# Principal.net
KiCad netlist of a schematic drawn in EAGLE
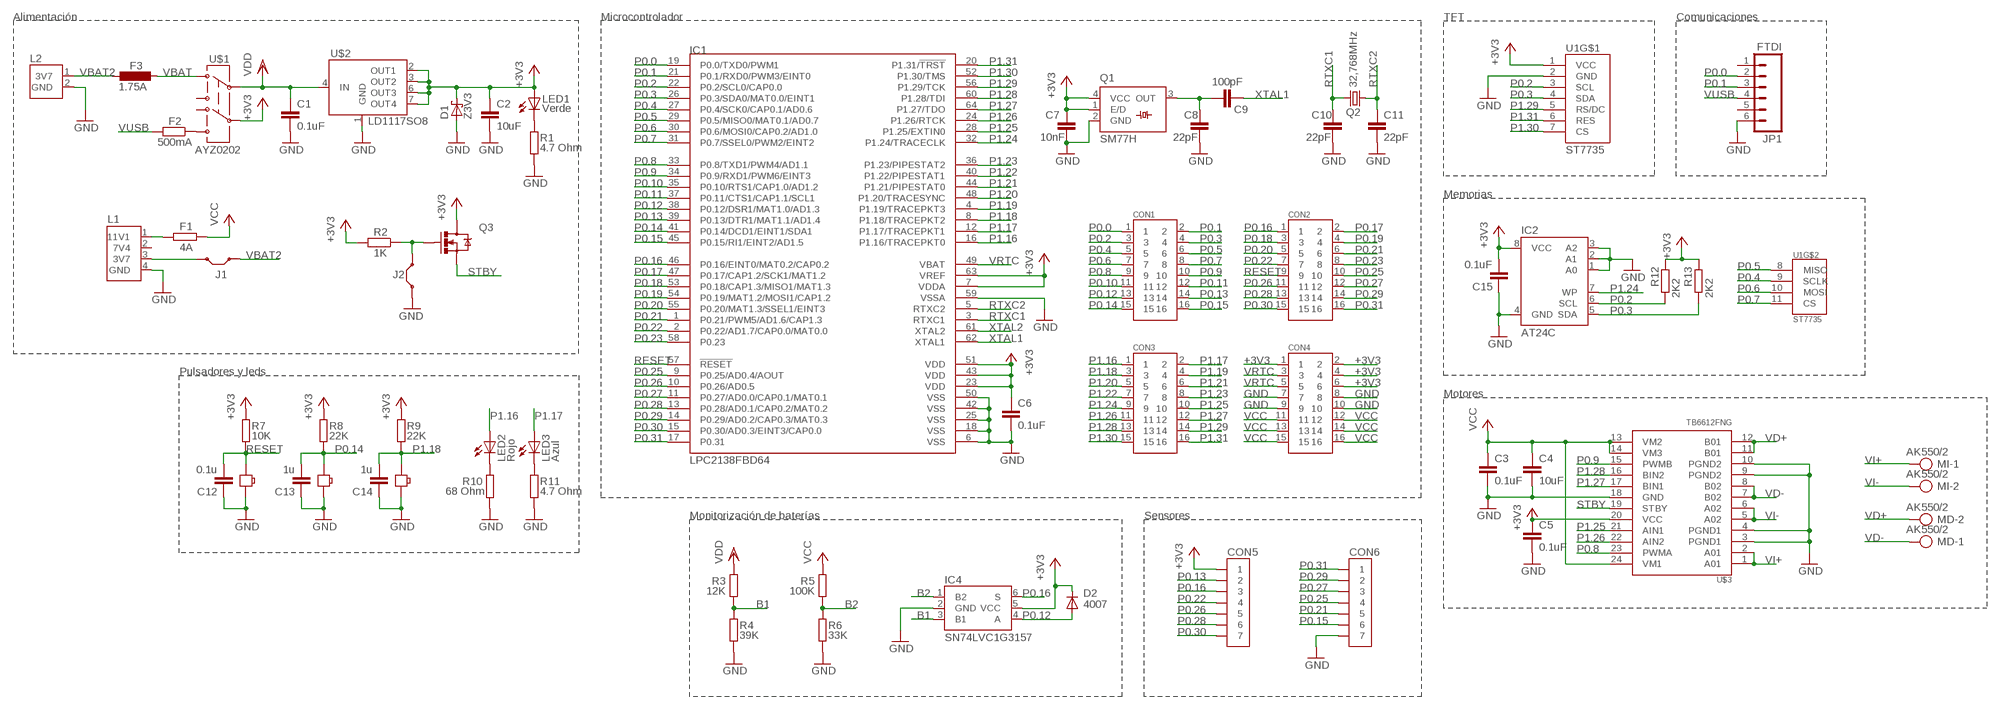
[diagram p0: schematic, sheet 1]

(export (version "E")
  (design (tool "Eeschema 10.0.6"))
  (components
    (comp (ref "B1")
      (value "BUTTON-SMD-2P")
      (footprint "eagle-import:BUTTON_2P_SMD")
      (libsource (lib "eagle-import") (part "BUTTON-SMD-2P"))
    )
    (comp (ref "C1")
      (value "0.1uF")
      (footprint "eagle-import:C0805")
      (libsource (lib "eagle-import") (part "C-EUC0805"))
    )
    (comp (ref "C2")
      (value "10uF")
      (footprint "eagle-import:C1206")
      (libsource (lib "eagle-import") (part "C-EUC1206"))
    )
    (comp (ref "C3")
      (value "0.1uF")
      (footprint "eagle-import:C0805")
      (libsource (lib "eagle-import") (part "C-EUC0805"))
    )
    (comp (ref "C4")
      (value "10uF")
      (footprint "eagle-import:C1206")
      (libsource (lib "eagle-import") (part "C-EUC1206"))
    )
    (comp (ref "C5")
      (value "0.1uF")
      (footprint "eagle-import:C0805")
      (libsource (lib "eagle-import") (part "C-EUC0805"))
    )
    (comp (ref "C6")
      (value "0.1uF")
      (footprint "eagle-import:C0805")
      (libsource (lib "eagle-import") (part "C-EUC0805"))
    )
    (comp (ref "C7")
      (value "10nF")
      (footprint "eagle-import:C0805")
      (libsource (lib "eagle-import") (part "C-EUC0805"))
    )
    (comp (ref "C8")
      (value "22pF")
      (footprint "eagle-import:C0805")
      (libsource (lib "eagle-import") (part "C-EUC0805"))
    )
    (comp (ref "C9")
      (value "100pF")
      (footprint "eagle-import:C0805")
      (libsource (lib "eagle-import") (part "C-EUC0805"))
    )
    (comp (ref "C10")
      (value "22pF")
      (footprint "eagle-import:C0805")
      (libsource (lib "eagle-import") (part "C-EUC0805"))
    )
    (comp (ref "C11")
      (value "22pF")
      (footprint "eagle-import:C0805")
      (libsource (lib "eagle-import") (part "C-EUC0805"))
    )
    (comp (ref "C12")
      (value "0.1u")
      (footprint "eagle-import:C0805")
      (libsource (lib "eagle-import") (part "C-EUC0805"))
    )
    (comp (ref "C13")
      (value "1u")
      (footprint "eagle-import:C0805")
      (libsource (lib "eagle-import") (part "C-EUC0805"))
    )
    (comp (ref "C14")
      (value "1u")
      (footprint "eagle-import:C0805")
      (libsource (lib "eagle-import") (part "C-EUC0805"))
    )
    (comp (ref "C15")
      (value "0.1uF")
      (footprint "eagle-import:C0805")
      (libsource (lib "eagle-import") (part "C-EUC0805"))
    )
    (comp (ref "CON1")
      (value "8X2_PIN_2MM_HEMBRA")
      (footprint "eagle-import:8X2_PIN_2MM")
      (libsource (lib "eagle-import") (part "8X2_PIN_2MM_HEMBRA"))
    )
    (comp (ref "CON2")
      (value "8X2_PIN_2MM_HEMBRA")
      (footprint "eagle-import:8X2_PIN_2MM")
      (libsource (lib "eagle-import") (part "8X2_PIN_2MM_HEMBRA"))
    )
    (comp (ref "CON3")
      (value "8X2_PIN_2MM_HEMBRA")
      (footprint "eagle-import:8X2_PIN_2MM")
      (libsource (lib "eagle-import") (part "8X2_PIN_2MM_HEMBRA"))
    )
    (comp (ref "CON4")
      (value "8X2_PIN_2MM_HEMBRA")
      (footprint "eagle-import:8X2_PIN_2MM")
      (libsource (lib "eagle-import") (part "8X2_PIN_2MM_HEMBRA"))
    )
    (comp (ref "CON5")
      (value "7_PINES")
      (footprint "eagle-import:7_PIN_MACHO_SMD_RA")
      (libsource (lib "eagle-import") (part "7_PINES"))
    )
    (comp (ref "CON6")
      (value "7_PINES")
      (footprint "eagle-import:7_PIN_MACHO_SMD_RA")
      (libsource (lib "eagle-import") (part "7_PINES"))
    )
    (comp (ref "D1")
      (value "Z3V3")
      (footprint "eagle-import:DO35-7")
      (libsource (lib "eagle-import") (part "SCHOTTKY-DIODEDO35-7"))
    )
    (comp (ref "D2")
      (value "4007")
      (footprint "eagle-import:SOD106-R")
      (libsource (lib "eagle-import") (part "DIODE-SOD106-R"))
    )
    (comp (ref "F1")
      (value "4A")
      (footprint "eagle-import:2920")
      (libsource (lib "eagle-import") (part "FUSIBLE"))
    )
    (comp (ref "F2")
      (value "500mA")
      (footprint "eagle-import:M1206")
      (libsource (lib "eagle-import") (part "R-EU_M1206"))
    )
    (comp (ref "F3")
      (value "1.75A")
      (footprint "eagle-import:L1812")
      (libsource (lib "eagle-import") (part "L-EUL1812"))
    )
    (comp (ref "IC1")
      (value "LPC2138FBD64")
      (footprint "eagle-import:TSQFP50P1200X1200X160-64N")
      (libsource (lib "eagle-import") (part "LPC2138FBD64"))
    )
    (comp (ref "IC2")
      (value "AT24C")
      (footprint "eagle-import:8S1")
      (libsource (lib "eagle-import") (part "AT24C"))
    )
    (comp (ref "IC4")
      (value "SN74LVC1G3157")
      (footprint "eagle-import:DBV")
      (libsource (lib "eagle-import") (part "SN74LVC1G3157"))
    )
    (comp (ref "J1")
      (value "JUMPERSMD")
      (footprint "eagle-import:2_PIN_VERT_SMD")
      (libsource (lib "eagle-import") (part "JUMPERSMD"))
    )
    (comp (ref "J2")
      (value "JUMPERSMD")
      (footprint "eagle-import:2_PIN_VERT_SMD")
      (libsource (lib "eagle-import") (part "JUMPERSMD"))
    )
    (comp (ref "JP1")
      (value "FTDI")
      (footprint "eagle-import:1X06_SMD_STRAIGHT")
      (libsource (lib "eagle-import") (part "M06SMD-STRAIGHT"))
    )
    (comp (ref "L1")
      (value "CONECTOR_LIPO_11.1V")
      (footprint "eagle-import:CONECTOR_LIPO_11.1V")
      (libsource (lib "eagle-import") (part "CONECTOR_LIPO_11.1V"))
    )
    (comp (ref "L2")
      (value "CONECTOR_LIPO_3.7V")
      (footprint "eagle-import:CONECTOR_LIPO_3.7V")
      (libsource (lib "eagle-import") (part "CONECTOR_LIPO_3.7V"))
    )
    (comp (ref "LED1")
      (value "Verde")
      (footprint "eagle-import:CHIPLED_0805")
      (libsource (lib "eagle-import") (part "LEDCHIPLED_0805"))
    )
    (comp (ref "LED2")
      (value "Rojo")
      (footprint "eagle-import:CHIPLED_0805")
      (libsource (lib "eagle-import") (part "LEDCHIPLED_0805"))
    )
    (comp (ref "LED3")
      (value "Azul")
      (footprint "eagle-import:CHIPLED_0805")
      (libsource (lib "eagle-import") (part "LEDCHIPLED_0805"))
    )
    (comp (ref "LOAD")
      (value "BUTTON-SMD-2P")
      (footprint "eagle-import:BUTTON_2P_SMD")
      (libsource (lib "eagle-import") (part "BUTTON-SMD-2P"))
    )
    (comp (ref "MD")
      (value "AK550/2")
      (footprint "eagle-import:AK550_2")
      (libsource (lib "eagle-import") (part "AK550/2"))
    )
    (comp (ref "MI")
      (value "AK550/2")
      (footprint "eagle-import:AK550_2")
      (libsource (lib "eagle-import") (part "AK550/2"))
    )
    (comp (ref "Q1")
      (value "SM77H")
      (footprint "eagle-import:SM77H")
      (libsource (lib "eagle-import") (part "SM77H"))
    )
    (comp (ref "Q2")
      (value "32,768MHz")
      (footprint "eagle-import:TC38H")
      (libsource (lib "eagle-import") (part "CRYSTALTC38H"))
    )
    (comp (ref "Q3")
      (value "MOSFET-NCHANNELSMD")
      (footprint "eagle-import:SOT23-3")
      (libsource (lib "eagle-import") (part "MOSFET-NCHANNELSMD"))
    )
    (comp (ref "R1")
      (value "4.7 Ohm")
      (footprint "eagle-import:R0805")
      (libsource (lib "eagle-import") (part "R-EU_R0805"))
    )
    (comp (ref "R2")
      (value "1K")
      (footprint "eagle-import:R0805")
      (libsource (lib "eagle-import") (part "R-EU_R0805"))
    )
    (comp (ref "R3")
      (value "12K")
      (footprint "eagle-import:R0805")
      (libsource (lib "eagle-import") (part "R-EU_R0805"))
    )
    (comp (ref "R4")
      (value "39K")
      (footprint "eagle-import:R0805")
      (libsource (lib "eagle-import") (part "R-EU_R0805"))
    )
    (comp (ref "R5")
      (value "100K")
      (footprint "eagle-import:R0805")
      (libsource (lib "eagle-import") (part "R-EU_R0805"))
    )
    (comp (ref "R6")
      (value "33K")
      (footprint "eagle-import:R0805")
      (libsource (lib "eagle-import") (part "R-EU_R0805"))
    )
    (comp (ref "R7")
      (value "10K")
      (footprint "eagle-import:R0805")
      (libsource (lib "eagle-import") (part "R-EU_R0805"))
    )
    (comp (ref "R8")
      (value "22K")
      (footprint "eagle-import:R0805")
      (libsource (lib "eagle-import") (part "R-EU_R0805"))
    )
    (comp (ref "R9")
      (value "22K")
      (footprint "eagle-import:R0805")
      (libsource (lib "eagle-import") (part "R-EU_R0805"))
    )
    (comp (ref "R10")
      (value "68 Ohm")
      (footprint "eagle-import:R0805")
      (libsource (lib "eagle-import") (part "R-EU_R0805"))
    )
    (comp (ref "R11")
      (value "4.7 Ohm")
      (footprint "eagle-import:R0805")
      (libsource (lib "eagle-import") (part "R-EU_R0805"))
    )
    (comp (ref "R12")
      (value "2K2")
      (footprint "eagle-import:R0805")
      (libsource (lib "eagle-import") (part "R-EU_R0805"))
    )
    (comp (ref "R13")
      (value "2K2")
      (footprint "eagle-import:R0805")
      (libsource (lib "eagle-import") (part "R-EU_R0805"))
    )
    (comp (ref "RESET")
      (value "BUTTON-SMD-2P")
      (footprint "eagle-import:BUTTON_2P_SMD")
      (libsource (lib "eagle-import") (part "BUTTON-SMD-2P"))
    )
    (comp (ref "U$1")
      (value "AYZ0202")
      (footprint "eagle-import:AYZ0202")
      (libsource (lib "eagle-import") (part "AYZ0202"))
    )
    (comp (ref "U$2")
      (value "LD1117SO8")
      (footprint "eagle-import:SO8")
      (libsource (lib "eagle-import") (part "LD1117SO8"))
    )
    (comp (ref "U$3")
      (value "TB6612FNG")
      (footprint "eagle-import:SSOP24")
      (libsource (lib "eagle-import") (part "TB6612FNG"))
    )
    (comp (ref "U1")
      (value "ST7735")
      (footprint "eagle-import:ST7735")
      (libsource (lib "eagle-import") (part "ST7735"))
    )
  )
  (nets
    (net (code "1") (name "+3V3") (class "Default")
      (node (ref "C15") (pin "2") (pinfunction "2_2") (pintype "passive"))
      (node (ref "C2") (pin "1") (pinfunction "1_1") (pintype "passive"))
      (node (ref "C5") (pin "1") (pinfunction "1_1") (pintype "passive"))
      (node (ref "C6") (pin "1") (pinfunction "1_1") (pintype "passive"))
      (node (ref "C7") (pin "1") (pinfunction "1_1") (pintype "passive"))
      (node (ref "CON4") (pin "1") (pinfunction "1_1") (pintype "bidirectional"))
      (node (ref "CON4") (pin "2") (pinfunction "2_2") (pintype "bidirectional"))
      (node (ref "CON4") (pin "4") (pinfunction "4_4") (pintype "bidirectional"))
      (node (ref "CON4") (pin "6") (pinfunction "6_6") (pintype "bidirectional"))
      (node (ref "CON5") (pin "P$1") (pinfunction "1_P$1") (pintype "bidirectional"))
      (node (ref "D1") (pin "C") (pinfunction "C_C") (pintype "passive"))
      (node (ref "D2") (pin "C") (pinfunction "C_C") (pintype "passive"))
      (node (ref "IC1") (pin "23") (pinfunction "VDD_23") (pintype "power_in"))
      (node (ref "IC1") (pin "43") (pinfunction "VDD_43") (pintype "power_in"))
      (node (ref "IC1") (pin "51") (pinfunction "VDD_51") (pintype "power_in"))
      (node (ref "IC1") (pin "63") (pinfunction "VREF_63") (pintype "input"))
      (node (ref "IC1") (pin "7") (pinfunction "VDDA_7") (pintype "power_in"))
      (node (ref "IC2") (pin "8") (pinfunction "VCC_8") (pintype "power_in"))
      (node (ref "IC4") (pin "5") (pinfunction "VCC_5") (pintype "power_in"))
      (node (ref "LED1") (pin "A") (pinfunction "A_A") (pintype "passive"))
      (node (ref "Q1") (pin "1") (pinfunction "E/D_1") (pintype "input"))
      (node (ref "Q1") (pin "4") (pinfunction "VCC_4") (pintype "power_in"))
      (node (ref "Q3") (pin "3") (pinfunction "D_3") (pintype "passive"))
      (node (ref "R12") (pin "2") (pinfunction "2_2") (pintype "passive"))
      (node (ref "R13") (pin "2") (pinfunction "2_2") (pintype "passive"))
      (node (ref "R2") (pin "2") (pinfunction "2_2") (pintype "passive"))
      (node (ref "R7") (pin "2") (pinfunction "2_2") (pintype "passive"))
      (node (ref "R8") (pin "2") (pinfunction "2_2") (pintype "passive"))
      (node (ref "R9") (pin "2") (pinfunction "2_2") (pintype "passive"))
      (node (ref "U$1") (pin "5") (pinfunction "5_5") (pintype "bidirectional"))
      (node (ref "U$2") (pin "2") (pinfunction "OUT1_2") (pintype "output"))
      (node (ref "U$2") (pin "3") (pinfunction "OUT2_3") (pintype "output"))
      (node (ref "U$2") (pin "6") (pinfunction "OUT3_6") (pintype "output"))
      (node (ref "U$2") (pin "7") (pinfunction "OUT4_7") (pintype "output"))
      (node (ref "U$3") (pin "20") (pinfunction "VCC_20") (pintype "bidirectional"))
      (node (ref "U1") (pin "1") (pinfunction "VCC_1") (pintype "power_in"))
    )
    (net (code "2") (name "/7V4") (class "Default")
      (node (ref "L1") (pin "2") (pinfunction "7V4_2") (pintype "power_in"))
    )
    (net (code "3") (name "/B1") (class "Default")
      (node (ref "IC4") (pin "3") (pinfunction "B1_3") (pintype "bidirectional"))
      (node (ref "R3") (pin "1") (pinfunction "1_1") (pintype "passive"))
      (node (ref "R4") (pin "2") (pinfunction "2_2") (pintype "passive"))
    )
    (net (code "4") (name "/B2") (class "Default")
      (node (ref "IC4") (pin "1") (pinfunction "B2_1") (pintype "bidirectional"))
      (node (ref "R5") (pin "1") (pinfunction "1_1") (pintype "passive"))
      (node (ref "R6") (pin "2") (pinfunction "2_2") (pintype "passive"))
    )
    (net (code "5") (name "/P0.0") (class "Default")
      (node (ref "CON1") (pin "1") (pinfunction "1_1") (pintype "bidirectional"))
      (node (ref "IC1") (pin "19") (pinfunction "P0.0/TXD0/PWM1_19") (pintype "bidirectional"))
      (node (ref "JP1") (pin "2") (pinfunction "2_2") (pintype "passive"))
    )
    (net (code "6") (name "/P0.1") (class "Default")
      (node (ref "CON1") (pin "2") (pinfunction "2_2") (pintype "bidirectional"))
      (node (ref "IC1") (pin "21") (pinfunction "P0.1/RXD0/PWM3/EINT0_21") (pintype "bidirectional"))
      (node (ref "JP1") (pin "3") (pinfunction "3_3") (pintype "passive"))
    )
    (net (code "7") (name "/P0.2") (class "Default")
      (node (ref "CON1") (pin "3") (pinfunction "3_3") (pintype "bidirectional"))
      (node (ref "IC1") (pin "22") (pinfunction "P0.2/SCL0/CAP0.0_22") (pintype "bidirectional"))
      (node (ref "IC2") (pin "6") (pinfunction "SCL_6") (pintype "bidirectional"))
      (node (ref "R12") (pin "1") (pinfunction "1_1") (pintype "passive"))
      (node (ref "U1") (pin "3") (pinfunction "SCL_3") (pintype "bidirectional"))
    )
    (net (code "8") (name "/P0.3") (class "Default")
      (node (ref "CON1") (pin "4") (pinfunction "4_4") (pintype "bidirectional"))
      (node (ref "IC1") (pin "26") (pinfunction "P0.3/SDA0/MAT0.0/EINT1_26") (pintype "bidirectional"))
      (node (ref "IC2") (pin "5") (pinfunction "SDA_5") (pintype "bidirectional"))
      (node (ref "R13") (pin "1") (pinfunction "1_1") (pintype "passive"))
      (node (ref "U1") (pin "4") (pinfunction "SDA_4") (pintype "bidirectional"))
    )
    (net (code "9") (name "/P0.4") (class "Default")
      (node (ref "CON1") (pin "5") (pinfunction "5_5") (pintype "bidirectional"))
      (node (ref "IC1") (pin "27") (pinfunction "P0.4/SCK0/CAP0.1/AD0.6_27") (pintype "bidirectional"))
      (node (ref "U1") (pin "9") (pinfunction "SCLK_9") (pintype "input"))
    )
    (net (code "10") (name "/P0.5") (class "Default")
      (node (ref "CON1") (pin "6") (pinfunction "6_6") (pintype "bidirectional"))
      (node (ref "IC1") (pin "29") (pinfunction "P0.5/MISO0/MAT0.1/AD0.7_29") (pintype "bidirectional"))
      (node (ref "U1") (pin "8") (pinfunction "MISO_8") (pintype "bidirectional"))
    )
    (net (code "11") (name "/P0.6") (class "Default")
      (node (ref "CON1") (pin "7") (pinfunction "7_7") (pintype "bidirectional"))
      (node (ref "IC1") (pin "30") (pinfunction "P0.6/MOSI0/CAP0.2/AD1.0_30") (pintype "bidirectional"))
      (node (ref "U1") (pin "10") (pinfunction "MOSI_10") (pintype "bidirectional"))
    )
    (net (code "12") (name "/P0.7") (class "Default")
      (node (ref "CON1") (pin "8") (pinfunction "8_8") (pintype "bidirectional"))
      (node (ref "IC1") (pin "31") (pinfunction "P0.7/SSEL0/PWM2/EINT2_31") (pintype "bidirectional"))
      (node (ref "U1") (pin "11") (pinfunction "CS_11") (pintype "input"))
    )
    (net (code "13") (name "/P0.8") (class "Default")
      (node (ref "CON1") (pin "9") (pinfunction "9_9") (pintype "bidirectional"))
      (node (ref "IC1") (pin "33") (pinfunction "P0.8/TXD1/PWM4/AD1.1_33") (pintype "bidirectional"))
      (node (ref "U$3") (pin "23") (pinfunction "PWMA_23") (pintype "bidirectional"))
    )
    (net (code "14") (name "/P0.9") (class "Default")
      (node (ref "CON1") (pin "10") (pinfunction "10_10") (pintype "bidirectional"))
      (node (ref "IC1") (pin "34") (pinfunction "P0.9/RXD1/PWM6/EINT3_34") (pintype "bidirectional"))
      (node (ref "U$3") (pin "15") (pinfunction "PWMB_15") (pintype "bidirectional"))
    )
    (net (code "15") (name "/P0.10") (class "Default")
      (node (ref "CON1") (pin "11") (pinfunction "11_11") (pintype "bidirectional"))
      (node (ref "IC1") (pin "35") (pinfunction "P0.10/RTS1/CAP1.0/AD1.2_35") (pintype "bidirectional"))
    )
    (net (code "16") (name "/P0.11") (class "Default")
      (node (ref "CON1") (pin "12") (pinfunction "12_12") (pintype "bidirectional"))
      (node (ref "IC1") (pin "37") (pinfunction "P0.11/CTS1/CAP1.1/SCL1_37") (pintype "bidirectional"))
    )
    (net (code "17") (name "/P0.12") (class "Default")
      (node (ref "CON1") (pin "13") (pinfunction "13_13") (pintype "bidirectional"))
      (node (ref "D2") (pin "A") (pinfunction "A_A") (pintype "passive"))
      (node (ref "IC1") (pin "38") (pinfunction "P0.12/DSR1/MAT1.0/AD1.3_38") (pintype "bidirectional"))
      (node (ref "IC4") (pin "4") (pinfunction "A_4") (pintype "bidirectional"))
    )
    (net (code "18") (name "/P0.13") (class "Default")
      (node (ref "CON1") (pin "14") (pinfunction "14_14") (pintype "bidirectional"))
      (node (ref "CON5") (pin "P$2") (pinfunction "2_P$2") (pintype "bidirectional"))
      (node (ref "IC1") (pin "39") (pinfunction "P0.13/DTR1/MAT1.1/AD1.4_39") (pintype "bidirectional"))
    )
    (net (code "19") (name "/P0.14") (class "Default")
      (node (ref "C13") (pin "2") (pinfunction "2_2") (pintype "passive"))
      (node (ref "CON1") (pin "15") (pinfunction "15_15") (pintype "bidirectional"))
      (node (ref "IC1") (pin "41") (pinfunction "P0.14/DCD1/EINT1/SDA1_41") (pintype "bidirectional"))
      (node (ref "LOAD") (pin "1") (pinfunction "P$1_1") (pintype "bidirectional"))
      (node (ref "R8") (pin "1") (pinfunction "1_1") (pintype "passive"))
    )
    (net (code "20") (name "/P0.15") (class "Default")
      (node (ref "CON1") (pin "16") (pinfunction "16_16") (pintype "bidirectional"))
      (node (ref "CON6") (pin "P$6") (pinfunction "6_P$6") (pintype "bidirectional"))
      (node (ref "IC1") (pin "45") (pinfunction "P0.15/RI1/EINT2/AD1.5_45") (pintype "bidirectional"))
    )
    (net (code "21") (name "/P0.16") (class "Default")
      (node (ref "CON2") (pin "1") (pinfunction "1_1") (pintype "bidirectional"))
      (node (ref "CON5") (pin "P$3") (pinfunction "3_P$3") (pintype "bidirectional"))
      (node (ref "IC1") (pin "46") (pinfunction "P0.16/EINT0/MAT0.2/CAP0.2_46") (pintype "bidirectional"))
      (node (ref "IC4") (pin "6") (pinfunction "S_6") (pintype "input"))
    )
    (net (code "22") (name "/P0.17") (class "Default")
      (node (ref "CON2") (pin "2") (pinfunction "2_2") (pintype "bidirectional"))
      (node (ref "IC1") (pin "47") (pinfunction "P0.17/CAP1.2/SCK1/MAT1.2_47") (pintype "bidirectional"))
    )
    (net (code "23") (name "/P0.18") (class "Default")
      (node (ref "CON2") (pin "3") (pinfunction "3_3") (pintype "bidirectional"))
      (node (ref "IC1") (pin "53") (pinfunction "P0.18/CAP1.3/MISO1/MAT1.3_53") (pintype "bidirectional"))
    )
    (net (code "24") (name "/P0.19") (class "Default")
      (node (ref "CON2") (pin "4") (pinfunction "4_4") (pintype "bidirectional"))
      (node (ref "IC1") (pin "54") (pinfunction "P0.19/MAT1.2/MOSI1/CAP1.2_54") (pintype "bidirectional"))
    )
    (net (code "25") (name "/P0.20") (class "Default")
      (node (ref "CON2") (pin "5") (pinfunction "5_5") (pintype "bidirectional"))
      (node (ref "IC1") (pin "55") (pinfunction "P0.20/MAT1.3/SSEL1/EINT3_55") (pintype "bidirectional"))
    )
    (net (code "26") (name "/P0.21") (class "Default")
      (node (ref "CON2") (pin "6") (pinfunction "6_6") (pintype "bidirectional"))
      (node (ref "CON6") (pin "P$5") (pinfunction "5_P$5") (pintype "bidirectional"))
      (node (ref "IC1") (pin "1") (pinfunction "P0.21/PWM5/AD1.6/CAP1.3_1") (pintype "bidirectional"))
    )
    (net (code "27") (name "/P0.22") (class "Default")
      (node (ref "CON2") (pin "7") (pinfunction "7_7") (pintype "bidirectional"))
      (node (ref "CON5") (pin "P$4") (pinfunction "4_P$4") (pintype "bidirectional"))
      (node (ref "IC1") (pin "2") (pinfunction "P0.22/AD1.7/CAP0.0/MAT0.0_2") (pintype "bidirectional"))
    )
    (net (code "28") (name "/P0.23") (class "Default")
      (node (ref "CON2") (pin "8") (pinfunction "8_8") (pintype "bidirectional"))
      (node (ref "IC1") (pin "58") (pinfunction "P0.23_58") (pintype "bidirectional"))
    )
    (net (code "29") (name "/P0.25") (class "Default")
      (node (ref "CON2") (pin "10") (pinfunction "10_10") (pintype "bidirectional"))
      (node (ref "CON6") (pin "P$4") (pinfunction "4_P$4") (pintype "bidirectional"))
      (node (ref "IC1") (pin "9") (pinfunction "P0.25/AD0.4/AOUT_9") (pintype "bidirectional"))
    )
    (net (code "30") (name "/P0.26") (class "Default")
      (node (ref "CON2") (pin "11") (pinfunction "11_11") (pintype "bidirectional"))
      (node (ref "CON5") (pin "P$5") (pinfunction "5_P$5") (pintype "bidirectional"))
      (node (ref "IC1") (pin "10") (pinfunction "P0.26/AD0.5_10") (pintype "bidirectional"))
    )
    (net (code "31") (name "/P0.27") (class "Default")
      (node (ref "CON2") (pin "12") (pinfunction "12_12") (pintype "bidirectional"))
      (node (ref "CON6") (pin "P$3") (pinfunction "3_P$3") (pintype "bidirectional"))
      (node (ref "IC1") (pin "11") (pinfunction "P0.27/AD0.0/CAP0.1/MAT0.1_11") (pintype "bidirectional"))
    )
    (net (code "32") (name "/P0.28") (class "Default")
      (node (ref "CON2") (pin "13") (pinfunction "13_13") (pintype "bidirectional"))
      (node (ref "CON5") (pin "P$6") (pinfunction "6_P$6") (pintype "bidirectional"))
      (node (ref "IC1") (pin "13") (pinfunction "P0.28/AD0.1/CAP0.2/MAT0.2_13") (pintype "bidirectional"))
    )
    (net (code "33") (name "/P0.29") (class "Default")
      (node (ref "CON2") (pin "14") (pinfunction "14_14") (pintype "bidirectional"))
      (node (ref "CON6") (pin "P$2") (pinfunction "2_P$2") (pintype "bidirectional"))
      (node (ref "IC1") (pin "14") (pinfunction "P0.29/AD0.2/CAP0.3/MAT0.3_14") (pintype "bidirectional"))
    )
    (net (code "34") (name "/P0.30") (class "Default")
      (node (ref "CON2") (pin "15") (pinfunction "15_15") (pintype "bidirectional"))
      (node (ref "CON5") (pin "P$7") (pinfunction "7_P$7") (pintype "bidirectional"))
      (node (ref "IC1") (pin "15") (pinfunction "P0.30/AD0.3/EINT3/CAP0.0_15") (pintype "bidirectional"))
    )
    (net (code "35") (name "/P0.31") (class "Default")
      (node (ref "CON2") (pin "16") (pinfunction "16_16") (pintype "bidirectional"))
      (node (ref "CON6") (pin "P$1") (pinfunction "1_P$1") (pintype "bidirectional"))
      (node (ref "IC1") (pin "17") (pinfunction "P0.31_17") (pintype "bidirectional"))
    )
    (net (code "36") (name "/P1.16") (class "Default")
      (node (ref "CON3") (pin "1") (pinfunction "1_1") (pintype "bidirectional"))
      (node (ref "IC1") (pin "16") (pinfunction "P1.16/TRACEPKT0_16") (pintype "bidirectional"))
      (node (ref "LED2") (pin "A") (pinfunction "A_A") (pintype "passive"))
    )
    (net (code "37") (name "/P1.17") (class "Default")
      (node (ref "CON3") (pin "2") (pinfunction "2_2") (pintype "bidirectional"))
      (node (ref "IC1") (pin "12") (pinfunction "P1.17/TRACEPKT1_12") (pintype "bidirectional"))
      (node (ref "LED3") (pin "A") (pinfunction "A_A") (pintype "passive"))
    )
    (net (code "38") (name "/P1.18") (class "Default")
      (node (ref "B1") (pin "1") (pinfunction "P$1_1") (pintype "bidirectional"))
      (node (ref "C14") (pin "2") (pinfunction "2_2") (pintype "passive"))
      (node (ref "CON3") (pin "3") (pinfunction "3_3") (pintype "bidirectional"))
      (node (ref "IC1") (pin "8") (pinfunction "P1.18/TRACEPKT2_8") (pintype "bidirectional"))
      (node (ref "R9") (pin "1") (pinfunction "1_1") (pintype "passive"))
    )
    (net (code "39") (name "/P1.19") (class "Default")
      (node (ref "CON3") (pin "4") (pinfunction "4_4") (pintype "bidirectional"))
      (node (ref "IC1") (pin "4") (pinfunction "P1.19/TRACEPKT3_4") (pintype "bidirectional"))
    )
    (net (code "40") (name "/P1.20") (class "Default")
      (node (ref "CON3") (pin "5") (pinfunction "5_5") (pintype "bidirectional"))
      (node (ref "IC1") (pin "48") (pinfunction "P1.20/TRACESYNC_48") (pintype "bidirectional"))
    )
    (net (code "41") (name "/P1.21") (class "Default")
      (node (ref "CON3") (pin "6") (pinfunction "6_6") (pintype "bidirectional"))
      (node (ref "IC1") (pin "44") (pinfunction "P1.21/PIPESTAT0_44") (pintype "bidirectional"))
    )
    (net (code "42") (name "/P1.22") (class "Default")
      (node (ref "CON3") (pin "7") (pinfunction "7_7") (pintype "bidirectional"))
      (node (ref "IC1") (pin "40") (pinfunction "P1.22/PIPESTAT1_40") (pintype "bidirectional"))
    )
    (net (code "43") (name "/P1.23") (class "Default")
      (node (ref "CON3") (pin "8") (pinfunction "8_8") (pintype "bidirectional"))
      (node (ref "IC1") (pin "36") (pinfunction "P1.23/PIPESTAT2_36") (pintype "bidirectional"))
    )
    (net (code "44") (name "/P1.24") (class "Default")
      (node (ref "CON3") (pin "9") (pinfunction "9_9") (pintype "bidirectional"))
      (node (ref "IC1") (pin "32") (pinfunction "P1.24/TRACECLK_32") (pintype "bidirectional"))
      (node (ref "IC2") (pin "7") (pinfunction "WP_7") (pintype "input"))
    )
    (net (code "45") (name "/P1.25") (class "Default")
      (node (ref "CON3") (pin "10") (pinfunction "10_10") (pintype "bidirectional"))
      (node (ref "IC1") (pin "28") (pinfunction "P1.25/EXTIN0_28") (pintype "bidirectional"))
      (node (ref "U$3") (pin "21") (pinfunction "AIN1_21") (pintype "bidirectional"))
    )
    (net (code "46") (name "/P1.26") (class "Default")
      (node (ref "CON3") (pin "11") (pinfunction "11_11") (pintype "bidirectional"))
      (node (ref "IC1") (pin "24") (pinfunction "P1.26/RTCK_24") (pintype "bidirectional"))
      (node (ref "U$3") (pin "22") (pinfunction "AIN2_22") (pintype "bidirectional"))
    )
    (net (code "47") (name "/P1.27") (class "Default")
      (node (ref "CON3") (pin "12") (pinfunction "12_12") (pintype "bidirectional"))
      (node (ref "IC1") (pin "64") (pinfunction "P1.27/TDO_64") (pintype "bidirectional"))
      (node (ref "U$3") (pin "17") (pinfunction "BIN1_17") (pintype "bidirectional"))
    )
    (net (code "48") (name "/P1.28") (class "Default")
      (node (ref "CON3") (pin "13") (pinfunction "13_13") (pintype "bidirectional"))
      (node (ref "IC1") (pin "60") (pinfunction "P1.28/TDI_60") (pintype "bidirectional"))
      (node (ref "U$3") (pin "16") (pinfunction "BIN2_16") (pintype "bidirectional"))
    )
    (net (code "49") (name "/P1.29") (class "Default")
      (node (ref "CON3") (pin "14") (pinfunction "14_14") (pintype "bidirectional"))
      (node (ref "IC1") (pin "56") (pinfunction "P1.29/TCK_56") (pintype "bidirectional"))
      (node (ref "U1") (pin "5") (pinfunction "RS/DC_5") (pintype "input"))
    )
    (net (code "50") (name "/P1.30") (class "Default")
      (node (ref "CON3") (pin "15") (pinfunction "15_15") (pintype "bidirectional"))
      (node (ref "IC1") (pin "52") (pinfunction "P1.30/TMS_52") (pintype "bidirectional"))
      (node (ref "U1") (pin "7") (pinfunction "CS_7") (pintype "input"))
    )
    (net (code "51") (name "/P1.31") (class "Default")
      (node (ref "CON3") (pin "16") (pinfunction "16_16") (pintype "bidirectional"))
      (node (ref "IC1") (pin "20") (pinfunction "P1.31/~{TRST}_20") (pintype "bidirectional"))
      (node (ref "U1") (pin "6") (pinfunction "RES_6") (pintype "input"))
    )
    (net (code "52") (name "/RESET") (class "Default")
      (node (ref "C12") (pin "2") (pinfunction "2_2") (pintype "passive"))
      (node (ref "CON2") (pin "9") (pinfunction "9_9") (pintype "bidirectional"))
      (node (ref "IC1") (pin "57") (pinfunction "~{RESET}_57") (pintype "input"))
      (node (ref "R7") (pin "1") (pinfunction "1_1") (pintype "passive"))
      (node (ref "RESET") (pin "1") (pinfunction "P$1_1") (pintype "bidirectional"))
    )
    (net (code "53") (name "/RTXC1") (class "Default")
      (node (ref "C10") (pin "1") (pinfunction "1_1") (pintype "passive"))
      (node (ref "IC1") (pin "3") (pinfunction "RTXC1_3") (pintype "input"))
      (node (ref "Q2") (pin "2") (pinfunction "2_2") (pintype "passive"))
    )
    (net (code "54") (name "/RTXC2") (class "Default")
      (node (ref "C11") (pin "1") (pinfunction "1_1") (pintype "passive"))
      (node (ref "IC1") (pin "5") (pinfunction "RTXC2_5") (pintype "output"))
      (node (ref "Q2") (pin "1") (pinfunction "1_1") (pintype "passive"))
    )
    (net (code "55") (name "/STBY") (class "Default")
      (node (ref "Q3") (pin "2") (pinfunction "S_2") (pintype "passive"))
      (node (ref "U$3") (pin "19") (pinfunction "STBY_19") (pintype "bidirectional"))
    )
    (net (code "56") (name "/VBAT") (class "Default")
      (node (ref "F3") (pin "1") (pinfunction "1_1") (pintype "passive"))
      (node (ref "U$1") (pin "3") (pinfunction "1_3") (pintype "bidirectional"))
    )
    (net (code "57") (name "/VBAT2") (class "Default")
      (node (ref "F3") (pin "2") (pinfunction "2_2") (pintype "passive"))
      (node (ref "J1") (pin "1") (pinfunction "1_1") (pintype "bidirectional"))
      (node (ref "L2") (pin "1") (pinfunction "3V7_1") (pintype "power_in"))
    )
    (net (code "58") (name "/VD+") (class "Default")
      (node (ref "MD") (pin "2") (pinfunction "KL_2") (pintype "passive"))
      (node (ref "U$3") (pin "11") (pinfunction "B01_11") (pintype "bidirectional"))
      (node (ref "U$3") (pin "12") (pinfunction "B01_12") (pintype "bidirectional"))
    )
    (net (code "59") (name "/VD-") (class "Default")
      (node (ref "MD") (pin "1") (pinfunction "KL_1") (pintype "passive"))
      (node (ref "U$3") (pin "7") (pinfunction "B02_7") (pintype "bidirectional"))
      (node (ref "U$3") (pin "8") (pinfunction "B02_8") (pintype "bidirectional"))
    )
    (net (code "60") (name "/VI+") (class "Default")
      (node (ref "MI") (pin "1") (pinfunction "KL_1") (pintype "passive"))
      (node (ref "U$3") (pin "1") (pinfunction "A01_1") (pintype "bidirectional"))
      (node (ref "U$3") (pin "2") (pinfunction "A01_2") (pintype "bidirectional"))
    )
    (net (code "61") (name "/VI-") (class "Default")
      (node (ref "MI") (pin "2") (pinfunction "KL_2") (pintype "passive"))
      (node (ref "U$3") (pin "5") (pinfunction "A02_5") (pintype "bidirectional"))
      (node (ref "U$3") (pin "6") (pinfunction "A02_6") (pintype "bidirectional"))
    )
    (net (code "62") (name "/VRTC") (class "Default")
      (node (ref "CON4") (pin "3") (pinfunction "3_3") (pintype "bidirectional"))
      (node (ref "CON4") (pin "5") (pinfunction "5_5") (pintype "bidirectional"))
      (node (ref "IC1") (pin "49") (pinfunction "VBAT_49") (pintype "power_in"))
    )
    (net (code "63") (name "/VUSB") (class "Default")
      (node (ref "F2") (pin "2") (pinfunction "2_2") (pintype "passive"))
      (node (ref "JP1") (pin "4") (pinfunction "4_4") (pintype "passive"))
    )
    (net (code "64") (name "/XTAL1") (class "Default")
      (node (ref "C9") (pin "2") (pinfunction "2_2") (pintype "passive"))
      (node (ref "IC1") (pin "62") (pinfunction "XTAL1_62") (pintype "input"))
    )
    (net (code "65") (name "/XTAL2") (class "Default")
      (node (ref "IC1") (pin "61") (pinfunction "XTAL2_61") (pintype "output"))
    )
    (net (code "66") (name "GND") (class "Default")
      (node (ref "B1") (pin "P$2") (pinfunction "P$2_P$2") (pintype "bidirectional"))
      (node (ref "C1") (pin "2") (pinfunction "2_2") (pintype "passive"))
      (node (ref "C10") (pin "2") (pinfunction "2_2") (pintype "passive"))
      (node (ref "C11") (pin "2") (pinfunction "2_2") (pintype "passive"))
      (node (ref "C12") (pin "1") (pinfunction "1_1") (pintype "passive"))
      (node (ref "C13") (pin "1") (pinfunction "1_1") (pintype "passive"))
      (node (ref "C14") (pin "1") (pinfunction "1_1") (pintype "passive"))
      (node (ref "C15") (pin "1") (pinfunction "1_1") (pintype "passive"))
      (node (ref "C2") (pin "2") (pinfunction "2_2") (pintype "passive"))
      (node (ref "C3") (pin "2") (pinfunction "2_2") (pintype "passive"))
      (node (ref "C4") (pin "2") (pinfunction "2_2") (pintype "passive"))
      (node (ref "C5") (pin "2") (pinfunction "2_2") (pintype "passive"))
      (node (ref "C6") (pin "2") (pinfunction "2_2") (pintype "passive"))
      (node (ref "C7") (pin "2") (pinfunction "2_2") (pintype "passive"))
      (node (ref "C8") (pin "2") (pinfunction "2_2") (pintype "passive"))
      (node (ref "CON4") (pin "10") (pinfunction "10_10") (pintype "bidirectional"))
      (node (ref "CON4") (pin "7") (pinfunction "7_7") (pintype "bidirectional"))
      (node (ref "CON4") (pin "8") (pinfunction "8_8") (pintype "bidirectional"))
      (node (ref "CON4") (pin "9") (pinfunction "9_9") (pintype "bidirectional"))
      (node (ref "CON6") (pin "P$7") (pinfunction "7_P$7") (pintype "bidirectional"))
      (node (ref "D1") (pin "A") (pinfunction "A_A") (pintype "passive"))
      (node (ref "IC1") (pin "18") (pinfunction "VSS_18") (pintype "power_in"))
      (node (ref "IC1") (pin "25") (pinfunction "VSS_25") (pintype "power_in"))
      (node (ref "IC1") (pin "42") (pinfunction "VSS_42") (pintype "power_in"))
      (node (ref "IC1") (pin "50") (pinfunction "VSS_50") (pintype "power_in"))
      (node (ref "IC1") (pin "59") (pinfunction "VSSA_59") (pintype "power_in"))
      (node (ref "IC1") (pin "6") (pinfunction "VSS_6") (pintype "power_in"))
      (node (ref "IC2") (pin "1") (pinfunction "A0_1") (pintype "input"))
      (node (ref "IC2") (pin "2") (pinfunction "A1_2") (pintype "input"))
      (node (ref "IC2") (pin "3") (pinfunction "A2_3") (pintype "input"))
      (node (ref "IC2") (pin "4") (pinfunction "GND_4") (pintype "power_in"))
      (node (ref "IC4") (pin "2") (pinfunction "GND_2") (pintype "power_in"))
      (node (ref "J2") (pin "1") (pinfunction "1_1") (pintype "bidirectional"))
      (node (ref "JP1") (pin "6") (pinfunction "6_6") (pintype "passive"))
      (node (ref "L1") (pin "4") (pinfunction "GND_4") (pintype "power_in"))
      (node (ref "L2") (pin "2") (pinfunction "GND_2") (pintype "power_in"))
      (node (ref "LOAD") (pin "P$2") (pinfunction "P$2_P$2") (pintype "bidirectional"))
      (node (ref "Q1") (pin "2") (pinfunction "GND_2") (pintype "power_in"))
      (node (ref "R1") (pin "2") (pinfunction "2_2") (pintype "passive"))
      (node (ref "R10") (pin "2") (pinfunction "2_2") (pintype "passive"))
      (node (ref "R11") (pin "2") (pinfunction "2_2") (pintype "passive"))
      (node (ref "R4") (pin "1") (pinfunction "1_1") (pintype "passive"))
      (node (ref "R6") (pin "1") (pinfunction "1_1") (pintype "passive"))
      (node (ref "RESET") (pin "P$2") (pinfunction "P$2_P$2") (pintype "bidirectional"))
      (node (ref "U$2") (pin "1") (pinfunction "GND_1") (pintype "power_in"))
      (node (ref "U$3") (pin "10") (pinfunction "PGND2_10") (pintype "bidirectional"))
      (node (ref "U$3") (pin "18") (pinfunction "GND_18") (pintype "bidirectional"))
      (node (ref "U$3") (pin "3") (pinfunction "PGND1_3") (pintype "bidirectional"))
      (node (ref "U$3") (pin "4") (pinfunction "PGND1_4") (pintype "bidirectional"))
      (node (ref "U$3") (pin "9") (pinfunction "PGND2_9") (pintype "bidirectional"))
      (node (ref "U1") (pin "2") (pinfunction "GND_2") (pintype "power_in"))
    )
    (net (code "67") (name "Net-(L1-3V7)") (class "Default")
      (node (ref "J1") (pin "2") (pinfunction "2_2") (pintype "bidirectional"))
      (node (ref "L1") (pin "3") (pinfunction "3V7_3") (pintype "power_in"))
    )
    (net (code "68") (name "Net-(L1-11V1)") (class "Default")
      (node (ref "F1") (pin "1") (pinfunction "1_1") (pintype "passive"))
      (node (ref "L1") (pin "1") (pinfunction "11V1_1") (pintype "power_in"))
    )
    (net (code "69") (name "Net-(LED1-PadC)") (class "Default")
      (node (ref "LED1") (pin "C") (pinfunction "C_C") (pintype "passive"))
      (node (ref "R1") (pin "1") (pinfunction "1_1") (pintype "passive"))
    )
    (net (code "70") (name "Net-(LED2-PadC)") (class "Default")
      (node (ref "LED2") (pin "C") (pinfunction "C_C") (pintype "passive"))
      (node (ref "R10") (pin "1") (pinfunction "1_1") (pintype "passive"))
    )
    (net (code "71") (name "Net-(LED3-PadC)") (class "Default")
      (node (ref "LED3") (pin "C") (pinfunction "C_C") (pintype "passive"))
      (node (ref "R11") (pin "1") (pinfunction "1_1") (pintype "passive"))
    )
    (net (code "72") (name "Net-(Q1-OUT)") (class "Default")
      (node (ref "C8") (pin "1") (pinfunction "1_1") (pintype "passive"))
      (node (ref "C9") (pin "1") (pinfunction "1_1") (pintype "passive"))
      (node (ref "Q1") (pin "3") (pinfunction "OUT_3") (pintype "output"))
    )
    (net (code "73") (name "Net-(Q3-G)") (class "Default")
      (node (ref "J2") (pin "2") (pinfunction "2_2") (pintype "bidirectional"))
      (node (ref "Q3") (pin "1") (pinfunction "G_1") (pintype "passive"))
      (node (ref "R2") (pin "1") (pinfunction "1_1") (pintype "passive"))
    )
    (net (code "74") (name "Net-(U$1-6)") (class "Default")
      (node (ref "F2") (pin "1") (pinfunction "1_1") (pintype "passive"))
      (node (ref "U$1") (pin "4") (pinfunction "6_4") (pintype "bidirectional"))
    )
    (net (code "75") (name "VCC") (class "Default")
      (node (ref "C3") (pin "1") (pinfunction "1_1") (pintype "passive"))
      (node (ref "C4") (pin "1") (pinfunction "1_1") (pintype "passive"))
      (node (ref "CON4") (pin "11") (pinfunction "11_11") (pintype "bidirectional"))
      (node (ref "CON4") (pin "12") (pinfunction "12_12") (pintype "bidirectional"))
      (node (ref "CON4") (pin "13") (pinfunction "13_13") (pintype "bidirectional"))
      (node (ref "CON4") (pin "14") (pinfunction "14_14") (pintype "bidirectional"))
      (node (ref "CON4") (pin "15") (pinfunction "15_15") (pintype "bidirectional"))
      (node (ref "CON4") (pin "16") (pinfunction "16_16") (pintype "bidirectional"))
      (node (ref "F1") (pin "2") (pinfunction "2_2") (pintype "passive"))
      (node (ref "R5") (pin "2") (pinfunction "2_2") (pintype "passive"))
      (node (ref "U$3") (pin "13") (pinfunction "VM2_13") (pintype "bidirectional"))
      (node (ref "U$3") (pin "14") (pinfunction "VM3_14") (pintype "bidirectional"))
      (node (ref "U$3") (pin "24") (pinfunction "VM1_24") (pintype "bidirectional"))
    )
    (net (code "76") (name "VDD") (class "Default")
      (node (ref "C1") (pin "1") (pinfunction "1_1") (pintype "passive"))
      (node (ref "R3") (pin "2") (pinfunction "2_2") (pintype "passive"))
      (node (ref "U$1") (pin "2") (pinfunction "2_2") (pintype "bidirectional"))
      (node (ref "U$2") (pin "4") (pinfunction "IN_4") (pintype "power_in"))
    )
    (net (code "77") (name "unconnected-(JP1-Pad1)") (class "Default")
      (node (ref "JP1") (pin "1") (pinfunction "1_1") (pintype "passive"))
    )
    (net (code "78") (name "unconnected-(JP1-Pad5)") (class "Default")
      (node (ref "JP1") (pin "5") (pinfunction "5_5") (pintype "passive"))
    )
    (net (code "79") (name "unconnected-(U$1-3-Pad1)") (class "Default")
      (node (ref "U$1") (pin "1") (pinfunction "3_1") (pintype "bidirectional"))
    )
    (net (code "80") (name "unconnected-(U$1-4-Pad6)") (class "Default")
      (node (ref "U$1") (pin "6") (pinfunction "4_6") (pintype "bidirectional"))
    )
  )
)
